# Sheet1.net
KiCad netlist of a schematic drawn in Altium Designer
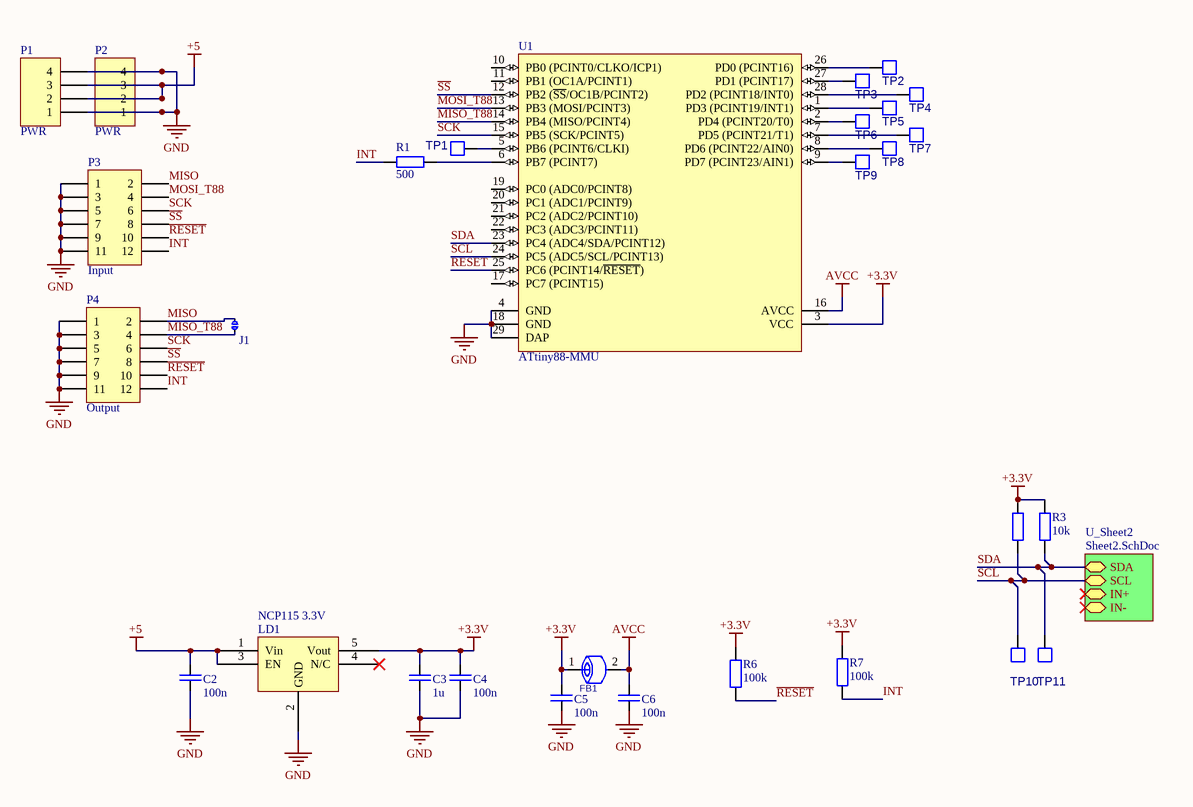
[diagram p0: Sheet1.SchDoc]

(export (version "E")
  (design (tool "Eeschema 10.0.6"))
  (components
    (comp (ref "C2")
      (value "100n")
      (footprint "R1005_0402i_L")
      (description "Capacitor")
      (libsource (lib "General") (part "C"))
    )
    (comp (ref "C3")
      (value "1u")
      (footprint "C1608_0603I_L")
      (description "Capacitor")
      (libsource (lib "General") (part "C"))
    )
    (comp (ref "C4")
      (value "100n")
      (footprint "R1005_0402i_L")
      (description "Capacitor")
      (libsource (lib "General") (part "C"))
    )
    (comp (ref "C5")
      (value "100n")
      (footprint "R1005_0402i_L")
      (description "Capacitor")
      (libsource (lib "General") (part "C"))
    )
    (comp (ref "C6")
      (value "100n")
      (footprint "R1005_0402i_L")
      (description "Capacitor")
      (libsource (lib "General") (part "C"))
    )
    (comp (ref "FB1")
      (value "FERITTE BEAD")
      (footprint "R1608_0603I_L")
      (libsource (lib "General") (part "FERITTE BEAD"))
    )
    (comp (ref "J1")
      (value "Terminator")
      (footprint "solderJumper")
      (libsource (lib "Kon_Tipk") (part "JMP_mini"))
    )
    (comp (ref "LD1")
      (value "NCP115 3.3V")
      (footprint "TSOP95P280X110-6L")
      (libsource (lib "led_ring") (part "NCP115 3.3V"))
    )
    (comp (ref "P1")
      (value "PWR")
      (footprint "HDR1X4")
      (description "Header, 4-Pin")
      (fields (field (name "PUBLISHER") "Altium Limited"))
      (libsource (lib "Miscellaneous Connectors") (part "Header 4"))
    )
    (comp (ref "P2")
      (value "PWR")
      (footprint "HDR1X4")
      (description "Header, 4-Pin")
      (fields (field (name "PUBLISHER") "Altium Limited"))
      (libsource (lib "Miscellaneous Connectors") (part "Header 4"))
    )
    (comp (ref "P3")
      (value "Input")
      (footprint "1.27mm SMD conn")
      (description "Header, 6-Pin, Dual row")
      (fields (field (name "PUBLISHER") "Altium Limited"))
      (libsource (lib "Miscellaneous Connectors") (part "Header 6X2"))
    )
    (comp (ref "P4")
      (value "Output")
      (footprint "1.27mm SMD conn")
      (description "Header, 6-Pin, Dual row")
      (fields (field (name "PUBLISHER") "Altium Limited"))
      (libsource (lib "Miscellaneous Connectors") (part "Header 6X2"))
    )
    (comp (ref "R1")
      (value "500")
      (footprint "R1005_0402i_L")
      (description "R")
      (libsource (lib "General") (part "R"))
    )
    (comp (ref "R2")
      (value "10k")
      (footprint "R1005_0402i_L")
      (description "R")
      (libsource (lib "General") (part "R"))
    )
    (comp (ref "R3")
      (value "10k")
      (footprint "R1005_0402i_L")
      (description "R")
      (libsource (lib "General") (part "R"))
    )
    (comp (ref "R6")
      (value "100k")
      (footprint "R1005_0402i_L")
      (description "R")
      (libsource (lib "General") (part "R"))
    )
    (comp (ref "R7")
      (value "100k")
      (footprint "R1005_0402i_L")
      (description "R")
      (libsource (lib "General") (part "R"))
    )
    (comp (ref "TP1") (value "PAD") (footprint "PAD") (libsource (lib "General") (part "PAD")))
    (comp (ref "TP2") (value "PAD") (footprint "PAD") (libsource (lib "General") (part "PAD")))
    (comp (ref "TP3") (value "PAD") (footprint "PAD") (libsource (lib "General") (part "PAD")))
    (comp (ref "TP4") (value "PAD") (footprint "PAD") (libsource (lib "General") (part "PAD")))
    (comp (ref "TP5") (value "PAD") (footprint "PAD") (libsource (lib "General") (part "PAD")))
    (comp (ref "TP6") (value "PAD") (footprint "PAD") (libsource (lib "General") (part "PAD")))
    (comp (ref "TP7") (value "PAD") (footprint "PAD") (libsource (lib "General") (part "PAD")))
    (comp (ref "TP8") (value "PAD") (footprint "PAD") (libsource (lib "General") (part "PAD")))
    (comp (ref "TP9") (value "PAD") (footprint "PAD") (libsource (lib "General") (part "PAD")))
    (comp (ref "TP10") (value "PAD") (footprint "PAD") (libsource (lib "General") (part "PAD")))
    (comp (ref "TP11") (value "PAD") (footprint "PAD") (libsource (lib "General") (part "PAD")))
    (comp (ref "U1")
      (value "ATtiny88-MMU")
      (footprint "28M1_N")
      (fields (field (name "PUBLISHER") "Altium Limited"))
      (libsource (lib "Atmel Microcontroller 8-Bit tinyAVR") (part "ATtiny88-MMU"))
    )
  )
  (nets
    (net (code "1") (name "+3.3V") (class "Default")
      (node (ref "C3") (pin "1") (pinfunction "1_1") (pintype "passive"))
      (node (ref "C4") (pin "1") (pinfunction "1_1") (pintype "passive"))
      (node (ref "C5") (pin "1") (pinfunction "1_1") (pintype "passive"))
      (node (ref "FB1") (pin "1") (pintype "passive"))
      (node (ref "LD1") (pin "5") (pinfunction "Vout_5") (pintype "passive"))
      (node (ref "R2") (pin "1") (pintype "passive"))
      (node (ref "R3") (pin "1") (pintype "passive"))
      (node (ref "R6") (pin "1") (pintype "passive"))
      (node (ref "R7") (pin "1") (pintype "passive"))
      (node (ref "U1") (pin "3") (pinfunction "VCC_3") (pintype "power_in"))
    )
    (net (code "2") (name "+5") (class "Default")
      (node (ref "C2") (pin "1") (pinfunction "1_1") (pintype "passive"))
      (node (ref "LD1") (pin "1") (pinfunction "Vin_1") (pintype "passive"))
      (node (ref "LD1") (pin "3") (pinfunction "EN_3") (pintype "passive"))
      (node (ref "P1") (pin "2") (pinfunction "2_2") (pintype "passive"))
      (node (ref "P1") (pin "3") (pinfunction "3_3") (pintype "passive"))
      (node (ref "P2") (pin "2") (pinfunction "2_2") (pintype "passive"))
      (node (ref "P2") (pin "3") (pinfunction "3_3") (pintype "passive"))
    )
    (net (code "5") (name "/INT") (class "Default")
      (node (ref "P3") (pin "12") (pinfunction "12_12") (pintype "passive"))
      (node (ref "P4") (pin "12") (pinfunction "12_12") (pintype "passive"))
      (node (ref "R1") (pin "1") (pintype "passive"))
      (node (ref "R7") (pin "2") (pintype "passive"))
    )
    (net (code "6") (name "/MISO") (class "Default")
      (node (ref "J1") (pin "2") (pinfunction "2_2") (pintype "passive"))
      (node (ref "P3") (pin "2") (pinfunction "2_2") (pintype "passive"))
      (node (ref "P4") (pin "2") (pinfunction "2_2") (pintype "passive"))
    )
    (net (code "7") (name "/MISO_T88") (class "Default")
      (node (ref "J1") (pin "1") (pinfunction "1_1") (pintype "passive"))
      (node (ref "P4") (pin "4") (pinfunction "4_4") (pintype "passive"))
      (node (ref "U1") (pin "14") (pinfunction "PB4_(MISO/PCINT4)_14") (pintype "bidirectional"))
    )
    (net (code "8") (name "/MOSI_T88") (class "Default")
      (node (ref "P3") (pin "4") (pinfunction "4_4") (pintype "passive"))
      (node (ref "U1") (pin "13") (pinfunction "PB3_(MOSI/PCINT3)_13") (pintype "bidirectional"))
    )
    (net (code "9") (name "/SCK") (class "Default")
      (node (ref "P3") (pin "6") (pinfunction "6_6") (pintype "passive"))
      (node (ref "P4") (pin "6") (pinfunction "6_6") (pintype "passive"))
      (node (ref "U1") (pin "15") (pinfunction "PB5_(SCK/PCINT5)_15") (pintype "bidirectional"))
    )
    (net (code "10") (name "/SCL") (class "Default")
      (node (ref "R2") (pin "2") (pintype "passive"))
      (node (ref "TP10") (pin "1") (pinfunction "1_1") (pintype "passive"))
      (node (ref "U1") (pin "24") (pinfunction "PC5_(ADC5/SCL/PCINT13)_24") (pintype "bidirectional"))
    )
    (net (code "11") (name "/SDA") (class "Default")
      (node (ref "R3") (pin "2") (pintype "passive"))
      (node (ref "TP11") (pin "1") (pinfunction "1_1") (pintype "passive"))
      (node (ref "U1") (pin "23") (pinfunction "PC4_(ADC4/SDA/PCINT12)_23") (pintype "bidirectional"))
    )
    (net (code "12") (name "/~{RESET}") (class "Default")
      (node (ref "P3") (pin "10") (pinfunction "10_10") (pintype "passive"))
      (node (ref "P4") (pin "10") (pinfunction "10_10") (pintype "passive"))
      (node (ref "R6") (pin "2") (pintype "passive"))
      (node (ref "U1") (pin "25") (pinfunction "PC6_(PCINT14/~{RESET})_25") (pintype "bidirectional"))
    )
    (net (code "13") (name "/~{SS}") (class "Default")
      (node (ref "P3") (pin "8") (pinfunction "8_8") (pintype "passive"))
      (node (ref "P4") (pin "8") (pinfunction "8_8") (pintype "passive"))
      (node (ref "U1") (pin "12") (pinfunction "PB2_(~{SS}/OC1B/PCINT2)_12") (pintype "bidirectional"))
    )
    (net (code "14") (name "AVCC") (class "Default")
      (node (ref "C6") (pin "1") (pinfunction "1_1") (pintype "passive"))
      (node (ref "FB1") (pin "2") (pintype "passive"))
      (node (ref "U1") (pin "16") (pinfunction "AVCC_16") (pintype "power_in"))
    )
    (net (code "15") (name "GND") (class "Default")
      (node (ref "C2") (pin "2") (pinfunction "2_2") (pintype "passive"))
      (node (ref "C3") (pin "2") (pinfunction "2_2") (pintype "passive"))
      (node (ref "C4") (pin "2") (pinfunction "2_2") (pintype "passive"))
      (node (ref "C5") (pin "2") (pinfunction "2_2") (pintype "passive"))
      (node (ref "C6") (pin "2") (pinfunction "2_2") (pintype "passive"))
      (node (ref "LD1") (pin "2") (pinfunction "GND_2") (pintype "passive"))
      (node (ref "P1") (pin "1") (pinfunction "1_1") (pintype "passive"))
      (node (ref "P1") (pin "4") (pinfunction "4_4") (pintype "passive"))
      (node (ref "P2") (pin "1") (pinfunction "1_1") (pintype "passive"))
      (node (ref "P2") (pin "4") (pinfunction "4_4") (pintype "passive"))
      (node (ref "P3") (pin "1") (pinfunction "1_1") (pintype "passive"))
      (node (ref "P3") (pin "11") (pinfunction "11_11") (pintype "passive"))
      (node (ref "P3") (pin "3") (pinfunction "3_3") (pintype "passive"))
      (node (ref "P3") (pin "5") (pinfunction "5_5") (pintype "passive"))
      (node (ref "P3") (pin "7") (pinfunction "7_7") (pintype "passive"))
      (node (ref "P3") (pin "9") (pinfunction "9_9") (pintype "passive"))
      (node (ref "P4") (pin "1") (pinfunction "1_1") (pintype "passive"))
      (node (ref "P4") (pin "11") (pinfunction "11_11") (pintype "passive"))
      (node (ref "P4") (pin "3") (pinfunction "3_3") (pintype "passive"))
      (node (ref "P4") (pin "5") (pinfunction "5_5") (pintype "passive"))
      (node (ref "P4") (pin "7") (pinfunction "7_7") (pintype "passive"))
      (node (ref "P4") (pin "9") (pinfunction "9_9") (pintype "passive"))
      (node (ref "U1") (pin "18") (pinfunction "GND_18") (pintype "power_in"))
      (node (ref "U1") (pin "29") (pinfunction "DAP_29") (pintype "passive"))
      (node (ref "U1") (pin "4") (pinfunction "GND_4") (pintype "power_in"))
    )
    (net (code "16") (name "Net-(U1-PB6_(PCINT6{slash}CLKI))") (class "Default")
      (node (ref "TP1") (pin "1") (pinfunction "1_1") (pintype "passive"))
      (node (ref "U1") (pin "5") (pinfunction "PB6_(PCINT6/CLKI)_5") (pintype "bidirectional"))
    )
    (net (code "17") (name "Net-(U1-PB7_(PCINT7))") (class "Default")
      (node (ref "R1") (pin "2") (pintype "passive"))
      (node (ref "U1") (pin "6") (pinfunction "PB7_(PCINT7)_6") (pintype "bidirectional"))
    )
    (net (code "18") (name "Net-(U1-PD0_(PCINT16))") (class "Default")
      (node (ref "TP2") (pin "1") (pinfunction "1_1") (pintype "passive"))
      (node (ref "U1") (pin "26") (pinfunction "PD0_(PCINT16)_26") (pintype "bidirectional"))
    )
    (net (code "19") (name "Net-(U1-PD1_(PCINT17))") (class "Default")
      (node (ref "TP3") (pin "1") (pinfunction "1_1") (pintype "passive"))
      (node (ref "U1") (pin "27") (pinfunction "PD1_(PCINT17)_27") (pintype "bidirectional"))
    )
    (net (code "20") (name "Net-(U1-PD2_(PCINT18{slash}INT0))") (class "Default")
      (node (ref "TP4") (pin "1") (pinfunction "1_1") (pintype "passive"))
      (node (ref "U1") (pin "28") (pinfunction "PD2_(PCINT18/INT0)_28") (pintype "bidirectional"))
    )
    (net (code "21") (name "Net-(U1-PD3_(PCINT19{slash}INT1))") (class "Default")
      (node (ref "TP5") (pin "1") (pinfunction "1_1") (pintype "passive"))
      (node (ref "U1") (pin "1") (pinfunction "PD3_(PCINT19/INT1)_1") (pintype "bidirectional"))
    )
    (net (code "22") (name "Net-(U1-PD4_(PCINT20{slash}T0))") (class "Default")
      (node (ref "TP6") (pin "1") (pinfunction "1_1") (pintype "passive"))
      (node (ref "U1") (pin "2") (pinfunction "PD4_(PCINT20/T0)_2") (pintype "bidirectional"))
    )
    (net (code "23") (name "Net-(U1-PD5_(PCINT21{slash}T1))") (class "Default")
      (node (ref "TP7") (pin "1") (pinfunction "1_1") (pintype "passive"))
      (node (ref "U1") (pin "7") (pinfunction "PD5_(PCINT21/T1)_7") (pintype "bidirectional"))
    )
    (net (code "24") (name "Net-(U1-PD6_(PCINT22{slash}AIN0))") (class "Default")
      (node (ref "TP8") (pin "1") (pinfunction "1_1") (pintype "passive"))
      (node (ref "U1") (pin "8") (pinfunction "PD6_(PCINT22/AIN0)_8") (pintype "bidirectional"))
    )
    (net (code "25") (name "Net-(U1-PD7_(PCINT23{slash}AIN1))") (class "Default")
      (node (ref "TP9") (pin "1") (pinfunction "1_1") (pintype "passive"))
      (node (ref "U1") (pin "9") (pinfunction "PD7_(PCINT23/AIN1)_9") (pintype "bidirectional"))
    )
    (net (code "26") (name "unconnected-(LD1-N{slash}C-Pad4)") (class "Default")
      (node (ref "LD1") (pin "4") (pinfunction "N/C_4") (pintype "passive+no_connect"))
    )
    (net (code "27") (name "unconnected-(U1-PB0_(PCINT0{slash}CLKO{slash}ICP1)-Pad10)") (class "Default")
      (node (ref "U1") (pin "10") (pinfunction "PB0_(PCINT0/CLKO/ICP1)_10") (pintype "bidirectional"))
    )
    (net (code "28") (name "unconnected-(U1-PB1_(OC1A{slash}PCINT1)-Pad11)") (class "Default")
      (node (ref "U1") (pin "11") (pinfunction "PB1_(OC1A/PCINT1)_11") (pintype "bidirectional"))
    )
    (net (code "29") (name "unconnected-(U1-PC0_(ADC0{slash}PCINT8)-Pad19)") (class "Default")
      (node (ref "U1") (pin "19") (pinfunction "PC0_(ADC0/PCINT8)_19") (pintype "bidirectional"))
    )
    (net (code "30") (name "unconnected-(U1-PC1_(ADC1{slash}PCINT9)-Pad20)") (class "Default")
      (node (ref "U1") (pin "20") (pinfunction "PC1_(ADC1/PCINT9)_20") (pintype "bidirectional"))
    )
    (net (code "31") (name "unconnected-(U1-PC2_(ADC2{slash}PCINT10)-Pad21)") (class "Default")
      (node (ref "U1") (pin "21") (pinfunction "PC2_(ADC2/PCINT10)_21") (pintype "bidirectional"))
    )
    (net (code "32") (name "unconnected-(U1-PC3_(ADC3{slash}PCINT11)-Pad22)") (class "Default")
      (node (ref "U1") (pin "22") (pinfunction "PC3_(ADC3/PCINT11)_22") (pintype "bidirectional"))
    )
    (net (code "33") (name "unconnected-(U1-PC7_(PCINT15)-Pad17)") (class "Default")
      (node (ref "U1") (pin "17") (pinfunction "PC7_(PCINT15)_17") (pintype "bidirectional"))
    )
  )
)
